# 04-Ethernet.net
KiCad netlist of a schematic drawn in Altium Designer
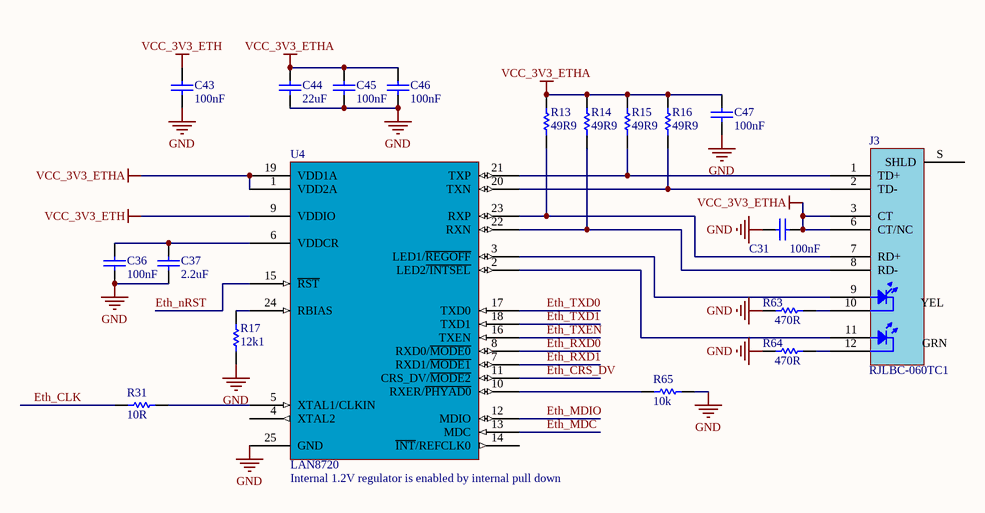
[diagram p0: 04-Ethernet.SchDoc]

(export (version "E")
  (design (tool "Eeschema 10.0.6"))
  (components
    (comp (ref "C31")
      (value "100nF")
      (footprint "Aptustech:CAPC1608X06N")
      (description "100nF 25V 0603 X5R")
      (fields (field (name "VOLTAGE") "25V") (field (name "TOLERANCE") "10%"))
      (libsource (lib "Cap_0603") (part "100nF 25V 0603 X5R"))
    )
    (comp (ref "C36")
      (value "100nF")
      (footprint "Aptustech:CAPC1608X06N")
      (description "100nF 25V 0603 X5R")
      (fields (field (name "VOLTAGE") "25V") (field (name "TOLERANCE") "10%"))
      (libsource (lib "Cap_0603") (part "100nF 25V 0603 X5R"))
    )
    (comp (ref "C37")
      (value "2.2uF")
      (footprint "Aptustech:CAPC1608X06N")
      (description "2.2uF 10V 0603 X5R")
      (fields (field (name "VOLTAGE") "10V") (field (name "TOLERANCE") "10%"))
      (libsource (lib "Cap_0603") (part "2.2uF 10V 0603 X5R"))
    )
    (comp (ref "C43")
      (value "100nF")
      (footprint "Aptustech:CAPC1608X06N")
      (description "100nF 25V 0603 X5R")
      (fields (field (name "VOLTAGE") "25V") (field (name "TOLERANCE") "10%"))
      (libsource (lib "Cap_0603") (part "100nF 25V 0603 X5R"))
    )
    (comp (ref "C44")
      (value "22uF")
      (footprint "Aptustech:CAPC1608X06N")
      (description "22uF 6.3V 0603 X5R")
      (fields (field (name "VOLTAGE") "6.3V") (field (name "TOLERANCE") "10%"))
      (libsource (lib "Cap_0603") (part "22uF 6.3V 0603 X5R"))
    )
    (comp (ref "C45")
      (value "100nF")
      (footprint "Aptustech:CAPC1608X06N")
      (description "100nF 25V 0603 X5R")
      (fields (field (name "VOLTAGE") "25V") (field (name "TOLERANCE") "10%"))
      (libsource (lib "Cap_0603") (part "100nF 25V 0603 X5R"))
    )
    (comp (ref "C46")
      (value "100nF")
      (footprint "Aptustech:CAPC1608X06N")
      (description "100nF 25V 0603 X5R")
      (fields (field (name "VOLTAGE") "25V") (field (name "TOLERANCE") "10%"))
      (libsource (lib "Cap_0603") (part "100nF 25V 0603 X5R"))
    )
    (comp (ref "C47")
      (value "100nF")
      (footprint "Aptustech:CAPC1608X06N")
      (description "100nF 25V 0603 X5R")
      (fields (field (name "VOLTAGE") "25V") (field (name "TOLERANCE") "10%"))
      (libsource (lib "Cap_0603") (part "100nF 25V 0603 X5R"))
    )
    (comp (ref "J3")
      (value "RJLBC-060TC1")
      (footprint "Aptustech:RJLBC-060TC1")
      (description "Modular Jack with Magnetics Shield LEDS  RJLBC-060TC1")
      (fields (field (name "MANUFACTURER") "TAIMAG"))
      (libsource (lib "Connectors") (part "RJLBC-060TC1"))
    )
    (comp (ref "R13")
      (value "49R9")
      (footprint "Aptustech:RESC1608X06N")
      (description "Resistor 49R9 0603 1%")
      (fields (field (name "TOLERANCE") "1%") (field (name "Comment") "49R9_0603"))
      (libsource (lib "Res_0603") (part "49R9"))
    )
    (comp (ref "R14")
      (value "49R9")
      (footprint "Aptustech:RESC1608X06N")
      (description "Resistor 49R9 0603 1%")
      (fields (field (name "TOLERANCE") "1%") (field (name "Comment") "49R9_0603"))
      (libsource (lib "Res_0603") (part "49R9"))
    )
    (comp (ref "R15")
      (value "49R9")
      (footprint "Aptustech:RESC1608X06N")
      (description "Resistor 49R9 0603 1%")
      (fields (field (name "TOLERANCE") "1%") (field (name "Comment") "49R9_0603"))
      (libsource (lib "Res_0603") (part "49R9"))
    )
    (comp (ref "R16")
      (value "49R9")
      (footprint "Aptustech:RESC1608X06N")
      (description "Resistor 49R9 0603 1%")
      (fields (field (name "TOLERANCE") "1%") (field (name "Comment") "49R9_0603"))
      (libsource (lib "Res_0603") (part "49R9"))
    )
    (comp (ref "R17")
      (value "12k1")
      (footprint "Aptustech:RESC1608X06N")
      (description "Resistor 12k1 0603 1%")
      (fields (field (name "TOLERANCE") "1%") (field (name "Comment") "12k1_0603"))
      (libsource (lib "Res_0603") (part "12k1"))
    )
    (comp (ref "R31")
      (value "10R")
      (footprint "Aptustech:RESC1608X06N")
      (description "Resistor 10R 0603 1%")
      (fields (field (name "TOLERANCE") "1%") (field (name "Comment") "10R_0603"))
      (libsource (lib "Res_0603") (part "10R"))
    )
    (comp (ref "R63")
      (value "470R")
      (footprint "Aptustech:RESC1608X06N")
      (description "Resistor 470R 0603 1%")
      (fields (field (name "TOLERANCE") "1%") (field (name "Comment") "470R_0603"))
      (libsource (lib "Res_0603") (part "470R"))
    )
    (comp (ref "R64")
      (value "470R")
      (footprint "Aptustech:RESC1608X06N")
      (description "Resistor 470R 0603 1%")
      (fields (field (name "TOLERANCE") "1%") (field (name "Comment") "470R_0603"))
      (libsource (lib "Res_0603") (part "470R"))
    )
    (comp (ref "R65")
      (value "10k")
      (footprint "RESC1608X06N")
      (description "Resistor 10k 0603 1%")
      (fields (field (name "TOLERANCE") "1%") (field (name "Comment") "10k_0603"))
      (libsource (lib "Res_0603") (part "10k"))
    )
    (comp (ref "U4")
      (value "LAN8720")
      (footprint "Aptustech:QFN50P400X400X100_HS-25N")
      (description "LAN8720 RMII 10/100 Ethernet  Transceiver QFN24")
      (fields (field (name "PARTNUMBER") "LAN8720A-CP-ABC") (field (name "MANUFACTURER") "Microchip"))
      (libsource (lib "MISC_IC") (part "LAN8720"))
    )
  )
  (nets
    (net (code "1") (name "/Eth_CLK") (class "Default")
      (node (ref "R31") (pin "1") (pinfunction "1_1") (pintype "passive"))
    )
    (net (code "2") (name "/Eth_CRS_DV") (class "Default")
      (node (ref "U4") (pin "11") (pinfunction "CRS_DV/~{MODE2}_11") (pintype "bidirectional"))
    )
    (net (code "3") (name "/Eth_MDC") (class "Default")
      (node (ref "U4") (pin "13") (pinfunction "MDC_13") (pintype "input"))
    )
    (net (code "4") (name "/Eth_MDIO") (class "Default")
      (node (ref "U4") (pin "12") (pinfunction "MDIO_12") (pintype "bidirectional"))
    )
    (net (code "5") (name "/Eth_RXD0") (class "Default")
      (node (ref "U4") (pin "8") (pinfunction "RXD0/~{MODE0}_8") (pintype "bidirectional"))
    )
    (net (code "6") (name "/Eth_RXD1") (class "Default")
      (node (ref "U4") (pin "7") (pinfunction "RXD1/~{MODE1}_7") (pintype "bidirectional"))
    )
    (net (code "7") (name "/Eth_TXD0") (class "Default")
      (node (ref "U4") (pin "17") (pinfunction "TXD0_17") (pintype "input"))
    )
    (net (code "8") (name "/Eth_TXD1") (class "Default")
      (node (ref "U4") (pin "18") (pinfunction "TXD1_18") (pintype "input"))
    )
    (net (code "9") (name "/Eth_TXEN") (class "Default")
      (node (ref "U4") (pin "16") (pinfunction "TXEN_16") (pintype "input"))
    )
    (net (code "10") (name "/Eth_nRST") (class "Default")
      (node (ref "U4") (pin "15") (pinfunction "~{RST}_15") (pintype "input"))
    )
    (net (code "11") (name "GND") (class "Default")
      (node (ref "C31") (pin "2") (pinfunction "2_2") (pintype "passive"))
      (node (ref "C36") (pin "2") (pinfunction "2_2") (pintype "passive"))
      (node (ref "C37") (pin "1") (pinfunction "1_1") (pintype "passive"))
      (node (ref "C43") (pin "2") (pinfunction "2_2") (pintype "passive"))
      (node (ref "C44") (pin "1") (pinfunction "1_1") (pintype "passive"))
      (node (ref "C45") (pin "2") (pinfunction "2_2") (pintype "passive"))
      (node (ref "C46") (pin "2") (pinfunction "2_2") (pintype "passive"))
      (node (ref "C47") (pin "2") (pinfunction "2_2") (pintype "passive"))
      (node (ref "R17") (pin "1") (pinfunction "1_1") (pintype "passive"))
      (node (ref "R63") (pin "1") (pinfunction "1_1") (pintype "passive"))
      (node (ref "R64") (pin "1") (pinfunction "1_1") (pintype "passive"))
      (node (ref "R65") (pin "1") (pinfunction "1_1") (pintype "passive"))
      (node (ref "U4") (pin "25") (pinfunction "GND_25") (pintype "power_in"))
    )
    (net (code "12") (name "Net-(J3-P9)") (class "Default")
      (node (ref "J3") (pin "9") (pinfunction "P9_9") (pintype "passive"))
      (node (ref "U4") (pin "3") (pinfunction "LED1/~{REGOFF}_3") (pintype "bidirectional"))
    )
    (net (code "13") (name "Net-(J3-P10)") (class "Default")
      (node (ref "J3") (pin "10") (pinfunction "P10_10") (pintype "passive"))
      (node (ref "R63") (pin "2") (pinfunction "2_2") (pintype "passive"))
    )
    (net (code "14") (name "Net-(J3-P11)") (class "Default")
      (node (ref "J3") (pin "11") (pinfunction "P11_11") (pintype "passive"))
      (node (ref "U4") (pin "2") (pinfunction "LED2~{/INTSEL}_2") (pintype "bidirectional"))
    )
    (net (code "15") (name "Net-(J3-P12)") (class "Default")
      (node (ref "J3") (pin "12") (pinfunction "P12_12") (pintype "passive"))
      (node (ref "R64") (pin "2") (pinfunction "2_2") (pintype "passive"))
    )
    (net (code "16") (name "Net-(J3-RD+)") (class "Default")
      (node (ref "J3") (pin "7") (pinfunction "RD+_7") (pintype "passive"))
      (node (ref "R13") (pin "1") (pinfunction "1_1") (pintype "passive"))
      (node (ref "U4") (pin "23") (pinfunction "RXP_23") (pintype "bidirectional"))
    )
    (net (code "17") (name "Net-(J3-RD-)") (class "Default")
      (node (ref "J3") (pin "8") (pinfunction "RD-_8") (pintype "passive"))
      (node (ref "R14") (pin "1") (pinfunction "1_1") (pintype "passive"))
      (node (ref "U4") (pin "22") (pinfunction "RXN_22") (pintype "bidirectional"))
    )
    (net (code "18") (name "Net-(J3-TD+)") (class "Default")
      (node (ref "J3") (pin "1") (pinfunction "TD+_1") (pintype "passive"))
      (node (ref "R15") (pin "1") (pinfunction "1_1") (pintype "passive"))
      (node (ref "U4") (pin "21") (pinfunction "TXP_21") (pintype "bidirectional"))
    )
    (net (code "19") (name "Net-(J3-TD-)") (class "Default")
      (node (ref "J3") (pin "2") (pinfunction "TD-_2") (pintype "passive"))
      (node (ref "R16") (pin "1") (pinfunction "1_1") (pintype "passive"))
      (node (ref "U4") (pin "20") (pinfunction "TXN_20") (pintype "bidirectional"))
    )
    (net (code "20") (name "Net-(U4-RBIAS)") (class "Default")
      (node (ref "R17") (pin "2") (pinfunction "2_2") (pintype "passive"))
      (node (ref "U4") (pin "24") (pinfunction "RBIAS_24") (pintype "input"))
    )
    (net (code "21") (name "Net-(U4-RXER{slash}~{PHYAD0})") (class "Default")
      (node (ref "R65") (pin "2") (pinfunction "2_2") (pintype "passive"))
      (node (ref "U4") (pin "10") (pinfunction "RXER/~{PHYAD0}_10") (pintype "bidirectional"))
    )
    (net (code "22") (name "Net-(U4-VDDCR)") (class "Default")
      (node (ref "C36") (pin "1") (pinfunction "1_1") (pintype "passive"))
      (node (ref "C37") (pin "2") (pinfunction "2_2") (pintype "passive"))
      (node (ref "U4") (pin "6") (pinfunction "VDDCR_6") (pintype "power_in"))
    )
    (net (code "23") (name "Net-(U4-XTAL1{slash}CLKIN)") (class "Default")
      (node (ref "R31") (pin "2") (pinfunction "2_2") (pintype "passive"))
      (node (ref "U4") (pin "5") (pinfunction "XTAL1/CLKIN_5") (pintype "input"))
    )
    (net (code "24") (name "VCC_3V3_ETH") (class "Default")
      (node (ref "C43") (pin "1") (pinfunction "1_1") (pintype "passive"))
      (node (ref "U4") (pin "9") (pinfunction "VDDIO_9") (pintype "power_in"))
    )
    (net (code "25") (name "VCC_3V3_ETHA") (class "Default")
      (node (ref "C31") (pin "1") (pinfunction "1_1") (pintype "passive"))
      (node (ref "C44") (pin "2") (pinfunction "2_2") (pintype "passive"))
      (node (ref "C45") (pin "1") (pinfunction "1_1") (pintype "passive"))
      (node (ref "C46") (pin "1") (pinfunction "1_1") (pintype "passive"))
      (node (ref "C47") (pin "1") (pinfunction "1_1") (pintype "passive"))
      (node (ref "J3") (pin "3") (pinfunction "CT_3") (pintype "passive"))
      (node (ref "J3") (pin "6") (pinfunction "CT/NC_6") (pintype "passive"))
      (node (ref "R13") (pin "2") (pinfunction "2_2") (pintype "passive"))
      (node (ref "R14") (pin "2") (pinfunction "2_2") (pintype "passive"))
      (node (ref "R15") (pin "2") (pinfunction "2_2") (pintype "passive"))
      (node (ref "R16") (pin "2") (pinfunction "2_2") (pintype "passive"))
      (node (ref "U4") (pin "1") (pinfunction "VDD2A_1") (pintype "power_in"))
      (node (ref "U4") (pin "19") (pinfunction "VDD1A_19") (pintype "power_in"))
    )
    (net (code "26") (name "unconnected-(J3-SHLD-PadS)") (class "Default")
      (node (ref "J3") (pin "S") (pinfunction "SHLD_S") (pintype "passive"))
    )
    (net (code "27") (name "unconnected-(U4-XTAL2-Pad4)") (class "Default")
      (node (ref "U4") (pin "4") (pinfunction "XTAL2_4") (pintype "output"))
    )
    (net (code "28") (name "unconnected-(U4-~{INT}{slash}REFCLK0-Pad14)") (class "Default")
      (node (ref "U4") (pin "14") (pinfunction "~{INT}/REFCLK0_14") (pintype "output"))
    )
  )
)
